# FMC_HPC2.net
KiCad netlist of a schematic drawn in Altium Designer
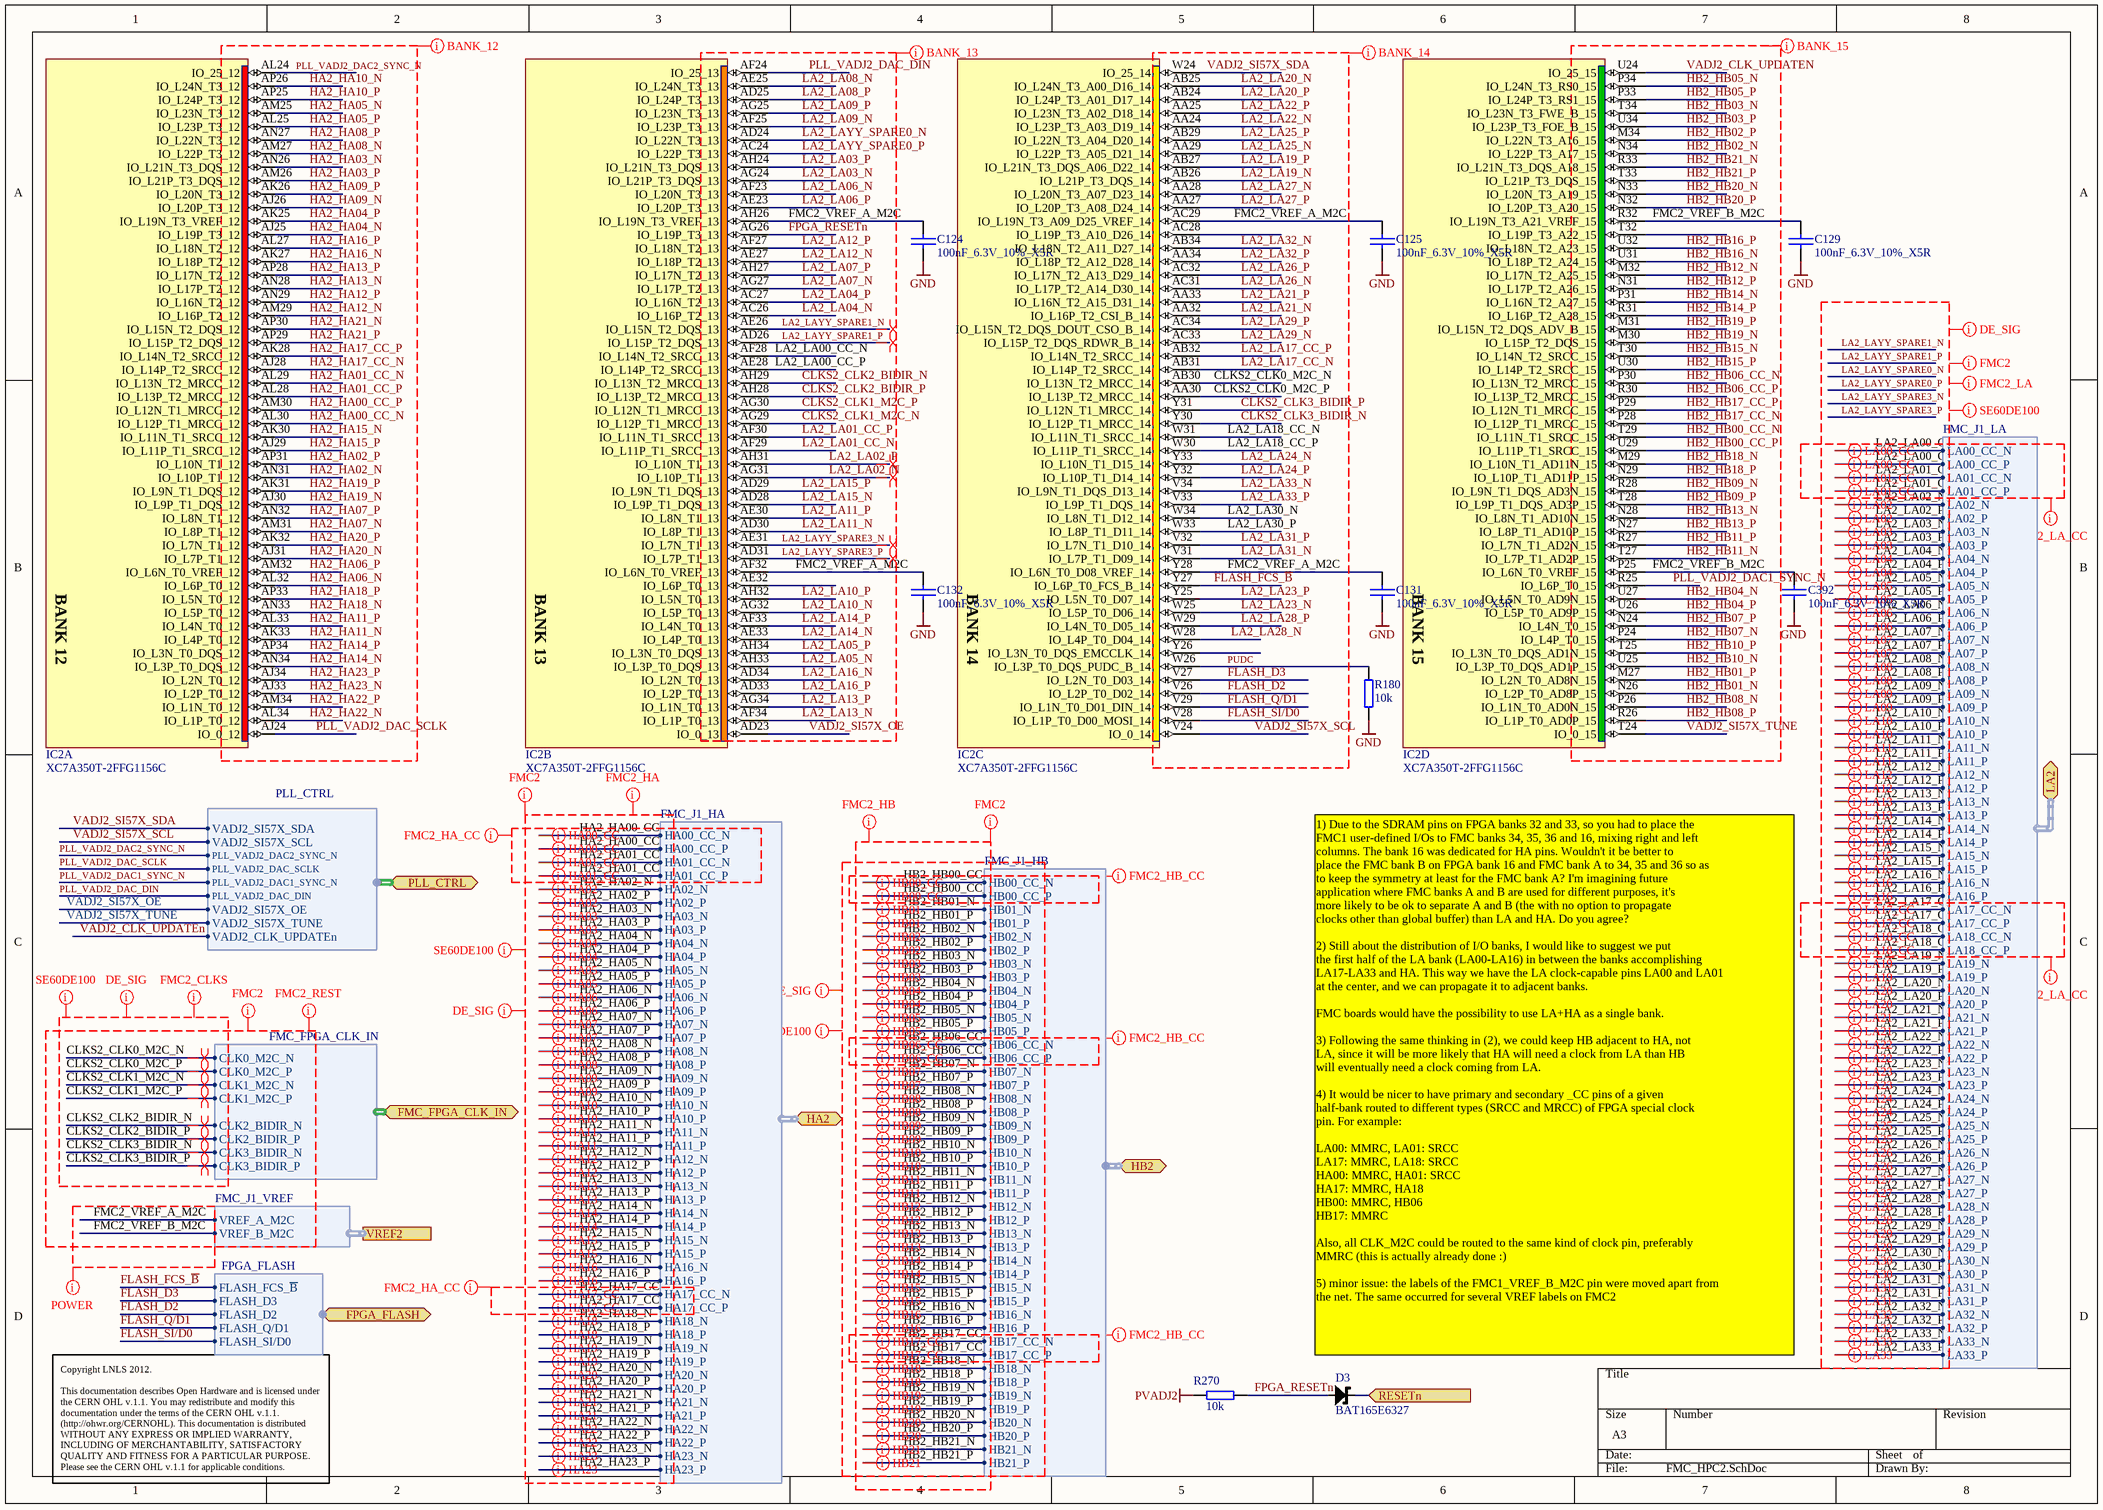
[diagram p0: FMC_HPC2.SchDoc]

(export (version "E")
  (design (tool "Eeschema 10.0.6"))
  (components
    (comp (ref "C124")
      (value "100nF_6.3V_10%_X5R")
      (footprint "0201C")
      (description "Capacitor SMD")
      (libsource (lib "LIBRARY_SCH") (part "CAP_SMD_0201"))
    )
    (comp (ref "C125")
      (value "100nF_6.3V_10%_X5R")
      (footprint "0201C")
      (description "Capacitor SMD")
      (libsource (lib "LIBRARY_SCH") (part "CAP_SMD_0201"))
    )
    (comp (ref "C129")
      (value "100nF_6.3V_10%_X5R")
      (footprint "0201C")
      (description "Capacitor SMD")
      (libsource (lib "LIBRARY_SCH") (part "CAP_SMD_0201"))
    )
    (comp (ref "C131")
      (value "100nF_6.3V_10%_X5R")
      (footprint "0201C")
      (description "Capacitor SMD")
      (libsource (lib "LIBRARY_SCH") (part "CAP_SMD_0201"))
    )
    (comp (ref "C132")
      (value "100nF_6.3V_10%_X5R")
      (footprint "0201C")
      (description "Capacitor SMD")
      (libsource (lib "LIBRARY_SCH") (part "CAP_SMD_0201"))
    )
    (comp (ref "C392")
      (value "100nF_6.3V_10%_X5R")
      (footprint "0201C")
      (description "Capacitor SMD")
      (libsource (lib "LIBRARY_SCH") (part "CAP_SMD_0201"))
    )
    (comp (ref "D3")
      (value "BAT165E6327")
      (footprint "SOD323")
      (description "500mA, 40V, Shottky Diode")
      (libsource (lib "LIBRARY_SCH") (part "D_BAT165"))
    )
    (comp (ref "IC2")
      (value "XC7A350T-2FFG1156C")
      (footprint "BGA1156C100P34X34_3500X3500X335")
      (description "Artix-6 FPGA, 16 GTPs, 600 User I/Os, 1156-Pin BGA, Speed Grade 2, Commercial Grade, Pb-Free")
      (fields (field (name "MANUFACTURER") "XILINX") (field (name "AUTHOR") "CERN DEM JLC"))
      (libsource (lib "AMC_FMC_Carrier") (part "XC7A350T-2FFG1156C"))
    )
    (comp (ref "R180")
      (value "10k")
      (footprint "0402R")
      (description "SMD Resistor")
      (libsource (lib "LIBRARY_SCH") (part "RES_0402"))
    )
    (comp (ref "R270")
      (value "10k")
      (footprint "0402R")
      (description "SMD Resistor")
      (libsource (lib "LIBRARY_SCH") (part "RES_0402"))
    )
  )
  (nets
    (net (code "8") (name "/CLKS2_CLK0_M2C_N") (class "Default")
      (node (ref "IC2") (pin "AB30") (pinfunction "IO_L13N_T2_MRCC_14_AB30") (pintype "bidirectional"))
    )
    (net (code "9") (name "/CLKS2_CLK0_M2C_P") (class "Default")
      (node (ref "IC2") (pin "AA30") (pinfunction "IO_L13P_T2_MRCC_14_AA30") (pintype "bidirectional"))
    )
    (net (code "10") (name "/CLKS2_CLK1_M2C_N") (class "Default")
      (node (ref "IC2") (pin "AG29") (pinfunction "IO_L12P_T1_MRCC_13_AG29") (pintype "bidirectional"))
    )
    (net (code "11") (name "/CLKS2_CLK1_M2C_P") (class "Default")
      (node (ref "IC2") (pin "AG30") (pinfunction "IO_L12N_T1_MRCC_13_AG30") (pintype "bidirectional"))
    )
    (net (code "12") (name "/CLKS2_CLK2_BIDIR_N") (class "Default")
      (node (ref "IC2") (pin "AH29") (pinfunction "IO_L13N_T2_MRCC_13_AH29") (pintype "bidirectional"))
    )
    (net (code "13") (name "/CLKS2_CLK2_BIDIR_P") (class "Default")
      (node (ref "IC2") (pin "AH28") (pinfunction "IO_L13P_T2_MRCC_13_AH28") (pintype "bidirectional"))
    )
    (net (code "14") (name "/CLKS2_CLK3_BIDIR_N") (class "Default")
      (node (ref "IC2") (pin "Y30") (pinfunction "IO_L12P_T1_MRCC_14_Y30") (pintype "bidirectional"))
    )
    (net (code "15") (name "/CLKS2_CLK3_BIDIR_P") (class "Default")
      (node (ref "IC2") (pin "Y31") (pinfunction "IO_L12N_T1_MRCC_14_Y31") (pintype "bidirectional"))
    )
    (net (code "16") (name "/FLASH_D2") (class "Default")
      (node (ref "IC2") (pin "V26") (pinfunction "IO_L2P_T0_D02_14_V26") (pintype "bidirectional"))
    )
    (net (code "17") (name "/FLASH_D3") (class "Default")
      (node (ref "IC2") (pin "V27") (pinfunction "IO_L2N_T0_D03_14_V27") (pintype "bidirectional"))
    )
    (net (code "18") (name "/FLASH_FCS_~{B}") (class "Default")
      (node (ref "IC2") (pin "Y27") (pinfunction "IO_L6P_T0_FCS_B_14_Y27") (pintype "bidirectional"))
    )
    (net (code "19") (name "/FLASH_Q{slash}D1") (class "Default")
      (node (ref "IC2") (pin "V29") (pinfunction "IO_L1N_T0_D01_DIN_14_V29") (pintype "bidirectional"))
    )
    (net (code "20") (name "/FLASH_SI{slash}D0") (class "Default")
      (node (ref "IC2") (pin "V28") (pinfunction "IO_L1P_T0_D00_MOSI_14_V28") (pintype "bidirectional"))
    )
    (net (code "21") (name "/FMC2_VREF_A_M2C") (class "Default")
      (node (ref "C124") (pin "1") (pinfunction "1_1") (pintype "passive"))
      (node (ref "C125") (pin "1") (pinfunction "1_1") (pintype "passive"))
      (node (ref "C131") (pin "1") (pinfunction "1_1") (pintype "passive"))
      (node (ref "C132") (pin "1") (pinfunction "1_1") (pintype "passive"))
      (node (ref "IC2") (pin "AC29") (pinfunction "IO_L19N_T3_A09_D25_VREF_14_AC29") (pintype "bidirectional"))
      (node (ref "IC2") (pin "AF32") (pinfunction "IO_L6N_T0_VREF_13_AF32") (pintype "bidirectional"))
      (node (ref "IC2") (pin "AH26") (pinfunction "IO_L19N_T3_VREF_13_AH26") (pintype "bidirectional"))
      (node (ref "IC2") (pin "Y28") (pinfunction "IO_L6N_T0_D08_VREF_14_Y28") (pintype "bidirectional"))
    )
    (net (code "22") (name "/FMC2_VREF_B_M2C") (class "Default")
      (node (ref "C129") (pin "1") (pinfunction "1_1") (pintype "passive"))
      (node (ref "C392") (pin "1") (pinfunction "1_1") (pintype "passive"))
      (node (ref "IC2") (pin "P25") (pinfunction "IO_L6N_T0_VREF_15_P25") (pintype "bidirectional"))
      (node (ref "IC2") (pin "R32") (pinfunction "IO_L19N_T3_A21_VREF_15_R32") (pintype "bidirectional"))
    )
    (net (code "23") (name "/FPGA_RESETn") (class "Default")
      (node (ref "D3") (pin "A") (pinfunction "A_A") (pintype "passive"))
      (node (ref "IC2") (pin "AG26") (pinfunction "IO_L19P_T3_13_AG26") (pintype "bidirectional"))
      (node (ref "R270") (pin "2") (pinfunction "2_2") (pintype "passive"))
    )
    (net (code "24") (name "/HA2_HA00_CC_N") (class "Default")
      (node (ref "IC2") (pin "AL30") (pinfunction "IO_L12P_T1_MRCC_12_AL30") (pintype "bidirectional"))
    )
    (net (code "25") (name "/HA2_HA00_CC_P") (class "Default")
      (node (ref "IC2") (pin "AM30") (pinfunction "IO_L12N_T1_MRCC_12_AM30") (pintype "bidirectional"))
    )
    (net (code "26") (name "/HA2_HA01_CC_N") (class "Default")
      (node (ref "IC2") (pin "AL29") (pinfunction "IO_L13N_T2_MRCC_12_AL29") (pintype "bidirectional"))
    )
    (net (code "27") (name "/HA2_HA01_CC_P") (class "Default")
      (node (ref "IC2") (pin "AL28") (pinfunction "IO_L13P_T2_MRCC_12_AL28") (pintype "bidirectional"))
    )
    (net (code "28") (name "/HA2_HA02_N") (class "Default")
      (node (ref "IC2") (pin "AN31") (pinfunction "IO_L10P_T1_12_AN31") (pintype "bidirectional"))
    )
    (net (code "29") (name "/HA2_HA02_P") (class "Default")
      (node (ref "IC2") (pin "AP31") (pinfunction "IO_L10N_T1_12_AP31") (pintype "bidirectional"))
    )
    (net (code "30") (name "/HA2_HA03_N") (class "Default")
      (node (ref "IC2") (pin "AN26") (pinfunction "IO_L21N_T3_DQS_12_AN26") (pintype "bidirectional"))
    )
    (net (code "31") (name "/HA2_HA03_P") (class "Default")
      (node (ref "IC2") (pin "AM26") (pinfunction "IO_L21P_T3_DQS_12_AM26") (pintype "bidirectional"))
    )
    (net (code "32") (name "/HA2_HA04_N") (class "Default")
      (node (ref "IC2") (pin "AJ25") (pinfunction "IO_L19P_T3_12_AJ25") (pintype "bidirectional"))
    )
    (net (code "33") (name "/HA2_HA04_P") (class "Default")
      (node (ref "IC2") (pin "AK25") (pinfunction "IO_L19N_T3_VREF_12_AK25") (pintype "bidirectional"))
    )
    (net (code "34") (name "/HA2_HA05_N") (class "Default")
      (node (ref "IC2") (pin "AM25") (pinfunction "IO_L23N_T3_12_AM25") (pintype "bidirectional"))
    )
    (net (code "35") (name "/HA2_HA05_P") (class "Default")
      (node (ref "IC2") (pin "AL25") (pinfunction "IO_L23P_T3_12_AL25") (pintype "bidirectional"))
    )
    (net (code "36") (name "/HA2_HA06_N") (class "Default")
      (node (ref "IC2") (pin "AL32") (pinfunction "IO_L6P_T0_12_AL32") (pintype "bidirectional"))
    )
    (net (code "37") (name "/HA2_HA06_P") (class "Default")
      (node (ref "IC2") (pin "AM32") (pinfunction "IO_L6N_T0_VREF_12_AM32") (pintype "bidirectional"))
    )
    (net (code "38") (name "/HA2_HA07_N") (class "Default")
      (node (ref "IC2") (pin "AM31") (pinfunction "IO_L8P_T1_12_AM31") (pintype "bidirectional"))
    )
    (net (code "39") (name "/HA2_HA07_P") (class "Default")
      (node (ref "IC2") (pin "AN32") (pinfunction "IO_L8N_T1_12_AN32") (pintype "bidirectional"))
    )
    (net (code "40") (name "/HA2_HA08_N") (class "Default")
      (node (ref "IC2") (pin "AM27") (pinfunction "IO_L22P_T3_12_AM27") (pintype "bidirectional"))
    )
    (net (code "41") (name "/HA2_HA08_P") (class "Default")
      (node (ref "IC2") (pin "AN27") (pinfunction "IO_L22N_T3_12_AN27") (pintype "bidirectional"))
    )
    (net (code "42") (name "/HA2_HA09_N") (class "Default")
      (node (ref "IC2") (pin "AJ26") (pinfunction "IO_L20P_T3_12_AJ26") (pintype "bidirectional"))
    )
    (net (code "43") (name "/HA2_HA09_P") (class "Default")
      (node (ref "IC2") (pin "AK26") (pinfunction "IO_L20N_T3_12_AK26") (pintype "bidirectional"))
    )
    (net (code "44") (name "/HA2_HA10_N") (class "Default")
      (node (ref "IC2") (pin "AP26") (pinfunction "IO_L24N_T3_12_AP26") (pintype "bidirectional"))
    )
    (net (code "45") (name "/HA2_HA10_P") (class "Default")
      (node (ref "IC2") (pin "AP25") (pinfunction "IO_L24P_T3_12_AP25") (pintype "bidirectional"))
    )
    (net (code "46") (name "/HA2_HA11_N") (class "Default")
      (node (ref "IC2") (pin "AK33") (pinfunction "IO_L4P_T0_12_AK33") (pintype "bidirectional"))
    )
    (net (code "47") (name "/HA2_HA11_P") (class "Default")
      (node (ref "IC2") (pin "AL33") (pinfunction "IO_L4N_T0_12_AL33") (pintype "bidirectional"))
    )
    (net (code "48") (name "/HA2_HA12_N") (class "Default")
      (node (ref "IC2") (pin "AM29") (pinfunction "IO_L16P_T2_12_AM29") (pintype "bidirectional"))
    )
    (net (code "49") (name "/HA2_HA12_P") (class "Default")
      (node (ref "IC2") (pin "AN29") (pinfunction "IO_L16N_T2_12_AN29") (pintype "bidirectional"))
    )
    (net (code "50") (name "/HA2_HA13_N") (class "Default")
      (node (ref "IC2") (pin "AN28") (pinfunction "IO_L17P_T2_12_AN28") (pintype "bidirectional"))
    )
    (net (code "51") (name "/HA2_HA13_P") (class "Default")
      (node (ref "IC2") (pin "AP28") (pinfunction "IO_L17N_T2_12_AP28") (pintype "bidirectional"))
    )
    (net (code "52") (name "/HA2_HA14_N") (class "Default")
      (node (ref "IC2") (pin "AN34") (pinfunction "IO_L3P_T0_DQS_12_AN34") (pintype "bidirectional"))
    )
    (net (code "53") (name "/HA2_HA14_P") (class "Default")
      (node (ref "IC2") (pin "AP34") (pinfunction "IO_L3N_T0_DQS_12_AP34") (pintype "bidirectional"))
    )
    (net (code "54") (name "/HA2_HA15_N") (class "Default")
      (node (ref "IC2") (pin "AK30") (pinfunction "IO_L11N_T1_SRCC_12_AK30") (pintype "bidirectional"))
    )
    (net (code "55") (name "/HA2_HA15_P") (class "Default")
      (node (ref "IC2") (pin "AJ29") (pinfunction "IO_L11P_T1_SRCC_12_AJ29") (pintype "bidirectional"))
    )
    (net (code "56") (name "/HA2_HA16_N") (class "Default")
      (node (ref "IC2") (pin "AK27") (pinfunction "IO_L18P_T2_12_AK27") (pintype "bidirectional"))
    )
    (net (code "57") (name "/HA2_HA16_P") (class "Default")
      (node (ref "IC2") (pin "AL27") (pinfunction "IO_L18N_T2_12_AL27") (pintype "bidirectional"))
    )
    (net (code "58") (name "/HA2_HA17_CC_N") (class "Default")
      (node (ref "IC2") (pin "AJ28") (pinfunction "IO_L14P_T2_SRCC_12_AJ28") (pintype "bidirectional"))
    )
    (net (code "59") (name "/HA2_HA17_CC_P") (class "Default")
      (node (ref "IC2") (pin "AK28") (pinfunction "IO_L14N_T2_SRCC_12_AK28") (pintype "bidirectional"))
    )
    (net (code "60") (name "/HA2_HA18_N") (class "Default")
      (node (ref "IC2") (pin "AN33") (pinfunction "IO_L5P_T0_12_AN33") (pintype "bidirectional"))
    )
    (net (code "61") (name "/HA2_HA18_P") (class "Default")
      (node (ref "IC2") (pin "AP33") (pinfunction "IO_L5N_T0_12_AP33") (pintype "bidirectional"))
    )
    (net (code "62") (name "/HA2_HA19_N") (class "Default")
      (node (ref "IC2") (pin "AJ30") (pinfunction "IO_L9P_T1_DQS_12_AJ30") (pintype "bidirectional"))
    )
    (net (code "63") (name "/HA2_HA19_P") (class "Default")
      (node (ref "IC2") (pin "AK31") (pinfunction "IO_L9N_T1_DQS_12_AK31") (pintype "bidirectional"))
    )
    (net (code "64") (name "/HA2_HA20_N") (class "Default")
      (node (ref "IC2") (pin "AJ31") (pinfunction "IO_L7P_T1_12_AJ31") (pintype "bidirectional"))
    )
    (net (code "65") (name "/HA2_HA20_P") (class "Default")
      (node (ref "IC2") (pin "AK32") (pinfunction "IO_L7N_T1_12_AK32") (pintype "bidirectional"))
    )
    (net (code "66") (name "/HA2_HA21_N") (class "Default")
      (node (ref "IC2") (pin "AP30") (pinfunction "IO_L15N_T2_DQS_12_AP30") (pintype "bidirectional"))
    )
    (net (code "67") (name "/HA2_HA21_P") (class "Default")
      (node (ref "IC2") (pin "AP29") (pinfunction "IO_L15P_T2_DQS_12_AP29") (pintype "bidirectional"))
    )
    (net (code "68") (name "/HA2_HA22_N") (class "Default")
      (node (ref "IC2") (pin "AL34") (pinfunction "IO_L1P_T0_12_AL34") (pintype "bidirectional"))
    )
    (net (code "69") (name "/HA2_HA22_P") (class "Default")
      (node (ref "IC2") (pin "AM34") (pinfunction "IO_L1N_T0_12_AM34") (pintype "bidirectional"))
    )
    (net (code "70") (name "/HA2_HA23_N") (class "Default")
      (node (ref "IC2") (pin "AJ33") (pinfunction "IO_L2P_T0_12_AJ33") (pintype "bidirectional"))
    )
    (net (code "71") (name "/HA2_HA23_P") (class "Default")
      (node (ref "IC2") (pin "AJ34") (pinfunction "IO_L2N_T0_12_AJ34") (pintype "bidirectional"))
    )
    (net (code "72") (name "/HB2_HB00_CC_N") (class "Default")
      (node (ref "IC2") (pin "T29") (pinfunction "IO_L11N_T1_SRCC_15_T29") (pintype "bidirectional"))
    )
    (net (code "73") (name "/HB2_HB00_CC_P") (class "Default")
      (node (ref "IC2") (pin "U29") (pinfunction "IO_L11P_T1_SRCC_15_U29") (pintype "bidirectional"))
    )
    (net (code "74") (name "/HB2_HB01_N") (class "Default")
      (node (ref "IC2") (pin "N26") (pinfunction "IO_L2P_T0_AD8P_15_N26") (pintype "bidirectional"))
    )
    (net (code "75") (name "/HB2_HB01_P") (class "Default")
      (node (ref "IC2") (pin "M27") (pinfunction "IO_L2N_T0_AD8N_15_M27") (pintype "bidirectional"))
    )
    (net (code "76") (name "/HB2_HB02_N") (class "Default")
      (node (ref "IC2") (pin "N34") (pinfunction "IO_L22P_T3_A17_15_N34") (pintype "bidirectional"))
    )
    (net (code "77") (name "/HB2_HB02_P") (class "Default")
      (node (ref "IC2") (pin "M34") (pinfunction "IO_L22N_T3_A16_15_M34") (pintype "bidirectional"))
    )
    (net (code "78") (name "/HB2_HB03_N") (class "Default")
      (node (ref "IC2") (pin "T34") (pinfunction "IO_L23N_T3_FWE_B_15_T34") (pintype "bidirectional"))
    )
    (net (code "79") (name "/HB2_HB03_P") (class "Default")
      (node (ref "IC2") (pin "U34") (pinfunction "IO_L23P_T3_FOE_B_15_U34") (pintype "bidirectional"))
    )
    (net (code "80") (name "/HB2_HB04_N") (class "Default")
      (node (ref "IC2") (pin "U27") (pinfunction "IO_L5N_T0_AD9N_15_U27") (pintype "bidirectional"))
    )
    (net (code "81") (name "/HB2_HB04_P") (class "Default")
      (node (ref "IC2") (pin "U26") (pinfunction "IO_L5P_T0_AD9P_15_U26") (pintype "bidirectional"))
    )
    (net (code "82") (name "/HB2_HB05_N") (class "Default")
      (node (ref "IC2") (pin "P34") (pinfunction "IO_L24N_T3_RS0_15_P34") (pintype "bidirectional"))
    )
    (net (code "83") (name "/HB2_HB05_P") (class "Default")
      (node (ref "IC2") (pin "P33") (pinfunction "IO_L24P_T3_RS1_15_P33") (pintype "bidirectional"))
    )
    (net (code "84") (name "/HB2_HB06_CC_N") (class "Default")
      (node (ref "IC2") (pin "P30") (pinfunction "IO_L13N_T2_MRCC_15_P30") (pintype "bidirectional"))
    )
    (net (code "85") (name "/HB2_HB06_CC_P") (class "Default")
      (node (ref "IC2") (pin "R30") (pinfunction "IO_L13P_T2_MRCC_15_R30") (pintype "bidirectional"))
    )
    (net (code "86") (name "/HB2_HB07_N") (class "Default")
      (node (ref "IC2") (pin "P24") (pinfunction "IO_L4P_T0_15_P24") (pintype "bidirectional"))
    )
    (net (code "87") (name "/HB2_HB07_P") (class "Default")
      (node (ref "IC2") (pin "N24") (pinfunction "IO_L4N_T0_15_N24") (pintype "bidirectional"))
    )
    (net (code "88") (name "/HB2_HB08_N") (class "Default")
      (node (ref "IC2") (pin "P26") (pinfunction "IO_L1N_T0_AD0N_15_P26") (pintype "bidirectional"))
    )
    (net (code "89") (name "/HB2_HB08_P") (class "Default")
      (node (ref "IC2") (pin "R26") (pinfunction "IO_L1P_T0_AD0P_15_R26") (pintype "bidirectional"))
    )
    (net (code "90") (name "/HB2_HB09_N") (class "Default")
      (node (ref "IC2") (pin "R28") (pinfunction "IO_L9N_T1_DQS_AD3N_15_R28") (pintype "bidirectional"))
    )
    (net (code "91") (name "/HB2_HB09_P") (class "Default")
      (node (ref "IC2") (pin "T28") (pinfunction "IO_L9P_T1_DQS_AD3P_15_T28") (pintype "bidirectional"))
    )
    (net (code "92") (name "/HB2_HB10_N") (class "Default")
      (node (ref "IC2") (pin "U25") (pinfunction "IO_L3P_T0_DQS_AD1P_15_U25") (pintype "bidirectional"))
    )
    (net (code "93") (name "/HB2_HB10_P") (class "Default")
      (node (ref "IC2") (pin "T25") (pinfunction "IO_L3N_T0_DQS_AD1N_15_T25") (pintype "bidirectional"))
    )
    (net (code "94") (name "/HB2_HB11_N") (class "Default")
      (node (ref "IC2") (pin "T27") (pinfunction "IO_L7P_T1_AD2P_15_T27") (pintype "bidirectional"))
    )
    (net (code "95") (name "/HB2_HB11_P") (class "Default")
      (node (ref "IC2") (pin "R27") (pinfunction "IO_L7N_T1_AD2N_15_R27") (pintype "bidirectional"))
    )
    (net (code "96") (name "/HB2_HB12_N") (class "Default")
      (node (ref "IC2") (pin "M32") (pinfunction "IO_L17N_T2_A25_15_M32") (pintype "bidirectional"))
    )
    (net (code "97") (name "/HB2_HB12_P") (class "Default")
      (node (ref "IC2") (pin "N31") (pinfunction "IO_L17P_T2_A26_15_N31") (pintype "bidirectional"))
    )
    (net (code "98") (name "/HB2_HB13_N") (class "Default")
      (node (ref "IC2") (pin "N28") (pinfunction "IO_L8N_T1_AD10N_15_N28") (pintype "bidirectional"))
    )
    (net (code "99") (name "/HB2_HB13_P") (class "Default")
      (node (ref "IC2") (pin "N27") (pinfunction "IO_L8P_T1_AD10P_15_N27") (pintype "bidirectional"))
    )
    (net (code "100") (name "/HB2_HB14_N") (class "Default")
      (node (ref "IC2") (pin "P31") (pinfunction "IO_L16N_T2_A27_15_P31") (pintype "bidirectional"))
    )
    (net (code "101") (name "/HB2_HB14_P") (class "Default")
      (node (ref "IC2") (pin "R31") (pinfunction "IO_L16P_T2_A28_15_R31") (pintype "bidirectional"))
    )
    (net (code "102") (name "/HB2_HB15_N") (class "Default")
      (node (ref "IC2") (pin "T30") (pinfunction "IO_L14N_T2_SRCC_15_T30") (pintype "bidirectional"))
    )
    (net (code "103") (name "/HB2_HB15_P") (class "Default")
      (node (ref "IC2") (pin "U30") (pinfunction "IO_L14P_T2_SRCC_15_U30") (pintype "bidirectional"))
    )
    (net (code "104") (name "/HB2_HB16_N") (class "Default")
      (node (ref "IC2") (pin "U31") (pinfunction "IO_L18P_T2_A24_15_U31") (pintype "bidirectional"))
    )
    (net (code "105") (name "/HB2_HB16_P") (class "Default")
      (node (ref "IC2") (pin "U32") (pinfunction "IO_L18N_T2_A23_15_U32") (pintype "bidirectional"))
    )
    (net (code "106") (name "/HB2_HB17_CC_N") (class "Default")
      (node (ref "IC2") (pin "P28") (pinfunction "IO_L12P_T1_MRCC_15_P28") (pintype "bidirectional"))
    )
    (net (code "107") (name "/HB2_HB17_CC_P") (class "Default")
      (node (ref "IC2") (pin "P29") (pinfunction "IO_L12N_T1_MRCC_15_P29") (pintype "bidirectional"))
    )
    (net (code "108") (name "/HB2_HB18_N") (class "Default")
      (node (ref "IC2") (pin "M29") (pinfunction "IO_L10N_T1_AD11N_15_M29") (pintype "bidirectional"))
    )
    (net (code "109") (name "/HB2_HB18_P") (class "Default")
      (node (ref "IC2") (pin "N29") (pinfunction "IO_L10P_T1_AD11P_15_N29") (pintype "bidirectional"))
    )
    (net (code "110") (name "/HB2_HB19_N") (class "Default")
      (node (ref "IC2") (pin "M30") (pinfunction "IO_L15P_T2_DQS_15_M30") (pintype "bidirectional"))
    )
    (net (code "111") (name "/HB2_HB19_P") (class "Default")
      (node (ref "IC2") (pin "M31") (pinfunction "IO_L15N_T2_DQS_ADV_B_15_M31") (pintype "bidirectional"))
    )
    (net (code "112") (name "/HB2_HB20_N") (class "Default")
      (node (ref "IC2") (pin "N33") (pinfunction "IO_L20N_T3_A19_15_N33") (pintype "bidirectional"))
    )
    (net (code "113") (name "/HB2_HB20_P") (class "Default")
      (node (ref "IC2") (pin "N32") (pinfunction "IO_L20P_T3_A20_15_N32") (pintype "bidirectional"))
    )
    (net (code "114") (name "/HB2_HB21_N") (class "Default")
      (node (ref "IC2") (pin "R33") (pinfunction "IO_L21N_T3_DQS_A18_15_R33") (pintype "bidirectional"))
    )
    (net (code "115") (name "/HB2_HB21_P") (class "Default")
      (node (ref "IC2") (pin "T33") (pinfunction "IO_L21P_T3_DQS_15_T33") (pintype "bidirectional"))
    )
    (net (code "116") (name "/LA2_LA00_CC_N") (class "Default")
      (node (ref "IC2") (pin "AF28") (pinfunction "IO_L14N_T2_SRCC_13_AF28") (pintype "bidirectional"))
    )
    (net (code "117") (name "/LA2_LA00_CC_P") (class "Default")
      (node (ref "IC2") (pin "AE28") (pinfunction "IO_L14P_T2_SRCC_13_AE28") (pintype "bidirectional"))
    )
    (net (code "118") (name "/LA2_LA01_CC_N") (class "Default")
      (node (ref "IC2") (pin "AF29") (pinfunction "IO_L11P_T1_SRCC_13_AF29") (pintype "bidirectional"))
    )
    (net (code "119") (name "/LA2_LA01_CC_P") (class "Default")
      (node (ref "IC2") (pin "AF30") (pinfunction "IO_L11N_T1_SRCC_13_AF30") (pintype "bidirectional"))
    )
    (net (code "120") (name "/LA2_LA02_N") (class "Default")
      (node (ref "IC2") (pin "AG31") (pinfunction "IO_L10P_T1_13_AG31") (pintype "bidirectional"))
    )
    (net (code "121") (name "/LA2_LA02_P") (class "Default")
      (node (ref "IC2") (pin "AH31") (pinfunction "IO_L10N_T1_13_AH31") (pintype "bidirectional"))
    )
    (net (code "122") (name "/LA2_LA03_N") (class "Default")
      (node (ref "IC2") (pin "AG24") (pinfunction "IO_L21P_T3_DQS_13_AG24") (pintype "bidirectional"))
    )
    (net (code "123") (name "/LA2_LA03_P") (class "Default")
      (node (ref "IC2") (pin "AH24") (pinfunction "IO_L21N_T3_DQS_13_AH24") (pintype "bidirectional"))
    )
    (net (code "124") (name "/LA2_LA04_N") (class "Default")
      (node (ref "IC2") (pin "AC26") (pinfunction "IO_L16P_T2_13_AC26") (pintype "bidirectional"))
    )
    (net (code "125") (name "/LA2_LA04_P") (class "Default")
      (node (ref "IC2") (pin "AC27") (pinfunction "IO_L16N_T2_13_AC27") (pintype "bidirectional"))
    )
    (net (code "126") (name "/LA2_LA05_N") (class "Default")
      (node (ref "IC2") (pin "AH33") (pinfunction "IO_L3P_T0_DQS_13_AH33") (pintype "bidirectional"))
    )
    (net (code "127") (name "/LA2_LA05_P") (class "Default")
      (node (ref "IC2") (pin "AH34") (pinfunction "IO_L3N_T0_DQS_13_AH34") (pintype "bidirectional"))
    )
    (net (code "128") (name "/LA2_LA06_N") (class "Default")
      (node (ref "IC2") (pin "AF23") (pinfunction "IO_L20N_T3_13_AF23") (pintype "bidirectional"))
    )
    (net (code "129") (name "/LA2_LA06_P") (class "Default")
      (node (ref "IC2") (pin "AE23") (pinfunction "IO_L20P_T3_13_AE23") (pintype "bidirectional"))
    )
    (net (code "130") (name "/LA2_LA07_N") (class "Default")
      (node (ref "IC2") (pin "AG27") (pinfunction "IO_L17P_T2_13_AG27") (pintype "bidirectional"))
    )
    (net (code "131") (name "/LA2_LA07_P") (class "Default")
      (node (ref "IC2") (pin "AH27") (pinfunction "IO_L17N_T2_13_AH27") (pintype "bidirectional"))
    )
    (net (code "132") (name "/LA2_LA08_N") (class "Default")
      (node (ref "IC2") (pin "AE25") (pinfunction "IO_L24N_T3_13_AE25") (pintype "bidirectional"))
    )
    (net (code "133") (name "/LA2_LA08_P") (class "Default")
      (node (ref "IC2") (pin "AD25") (pinfunction "IO_L24P_T3_13_AD25") (pintype "bidirectional"))
    )
    (net (code "134") (name "/LA2_LA09_N") (class "Default")
      (node (ref "IC2") (pin "AF25") (pinfunction "IO_L23P_T3_13_AF25") (pintype "bidirectional"))
    )
    (net (code "135") (name "/LA2_LA09_P") (class "Default")
      (node (ref "IC2") (pin "AG25") (pinfunction "IO_L23N_T3_13_AG25") (pintype "bidirectional"))
    )
    (net (code "136") (name "/LA2_LA10_N") (class "Default")
      (node (ref "IC2") (pin "AG32") (pinfunction "IO_L5P_T0_13_AG32") (pintype "bidirectional"))
    )
    (net (code "137") (name "/LA2_LA10_P") (class "Default")
      (node (ref "IC2") (pin "AH32") (pinfunction "IO_L5N_T0_13_AH32") (pintype "bidirectional"))
    )
    (net (code "138") (name "/LA2_LA11_N") (class "Default")
      (node (ref "IC2") (pin "AD30") (pinfunction "IO_L8P_T1_13_AD30") (pintype "bidirectional"))
    )
    (net (code "139") (name "/LA2_LA11_P") (class "Default")
      (node (ref "IC2") (pin "AE30") (pinfunction "IO_L8N_T1_13_AE30") (pintype "bidirectional"))
    )
    (net (code "140") (name "/LA2_LA12_N") (class "Default")
      (node (ref "IC2") (pin "AE27") (pinfunction "IO_L18P_T2_13_AE27") (pintype "bidirectional"))
    )
    (net (code "141") (name "/LA2_LA12_P") (class "Default")
      (node (ref "IC2") (pin "AF27") (pinfunction "IO_L18N_T2_13_AF27") (pintype "bidirectional"))
    )
    (net (code "142") (name "/LA2_LA13_N") (class "Default")
      (node (ref "IC2") (pin "AF34") (pinfunction "IO_L1P_T0_13_AF34") (pintype "bidirectional"))
    )
    (net (code "143") (name "/LA2_LA13_P") (class "Default")
      (node (ref "IC2") (pin "AG34") (pinfunction "IO_L1N_T0_13_AG34") (pintype "bidirectional"))
    )
    (net (code "144") (name "/LA2_LA14_N") (class "Default")
      (node (ref "IC2") (pin "AE33") (pinfunction "IO_L4P_T0_13_AE33") (pintype "bidirectional"))
    )
    (net (code "145") (name "/LA2_LA14_P") (class "Default")
      (node (ref "IC2") (pin "AF33") (pinfunction "IO_L4N_T0_13_AF33") (pintype "bidirectional"))
    )
    (net (code "146") (name "/LA2_LA15_N") (class "Default")
      (node (ref "IC2") (pin "AD28") (pinfunction "IO_L9P_T1_DQS_13_AD28") (pintype "bidirectional"))
    )
    (net (code "147") (name "/LA2_LA15_P") (class "Default")
      (node (ref "IC2") (pin "AD29") (pinfunction "IO_L9N_T1_DQS_13_AD29") (pintype "bidirectional"))
    )
    (net (code "148") (name "/LA2_LA16_N") (class "Default")
      (node (ref "IC2") (pin "AD34") (pinfunction "IO_L2N_T0_13_AD34") (pintype "bidirectional"))
    )
    (net (code "149") (name "/LA2_LA16_P") (class "Default")
      (node (ref "IC2") (pin "AD33") (pinfunction "IO_L2P_T0_13_AD33") (pintype "bidirectional"))
    )
    (net (code "150") (name "/LA2_LA17_CC_N") (class "Default")
      (node (ref "IC2") (pin "AB31") (pinfunction "IO_L14P_T2_SRCC_14_AB31") (pintype "bidirectional"))
    )
    (net (code "151") (name "/LA2_LA17_CC_P") (class "Default")
      (node (ref "IC2") (pin "AB32") (pinfunction "IO_L14N_T2_SRCC_14_AB32") (pintype "bidirectional"))
    )
    (net (code "152") (name "/LA2_LA18_CC_N") (class "Default")
      (node (ref "IC2") (pin "W31") (pinfunction "IO_L11N_T1_SRCC_14_W31") (pintype "bidirectional"))
    )
    (net (code "153") (name "/LA2_LA18_CC_P") (class "Default")
      (node (ref "IC2") (pin "W30") (pinfunction "IO_L11P_T1_SRCC_14_W30") (pintype "bidirectional"))
    )
    (net (code "154") (name "/LA2_LA19_N") (class "Default")
      (node (ref "IC2") (pin "AB26") (pinfunction "IO_L21P_T3_DQS_14_AB26") (pintype "bidirectional"))
    )
    (net (code "155") (name "/LA2_LA19_P") (class "Default")
      (node (ref "IC2") (pin "AB27") (pinfunction "IO_L21N_T3_DQS_A06_D22_14_AB27") (pintype "bidirectional"))
    )
    (net (code "156") (name "/LA2_LA20_N") (class "Default")
      (node (ref "IC2") (pin "AB25") (pinfunction "IO_L24N_T3_A00_D16_14_AB25") (pintype "bidirectional"))
    )
    (net (code "157") (name "/LA2_LA20_P") (class "Default")
      (node (ref "IC2") (pin "AB24") (pinfunction "IO_L24P_T3_A01_D17_14_AB24") (pintype "bidirectional"))
    )
    (net (code "158") (name "/LA2_LA21_N") (class "Default")
      (node (ref "IC2") (pin "AA32") (pinfunction "IO_L16P_T2_CSI_B_14_AA32") (pintype "bidirectional"))
    )
    (net (code "159") (name "/LA2_LA21_P") (class "Default")
      (node (ref "IC2") (pin "AA33") (pinfunction "IO_L16N_T2_A15_D31_14_AA33") (pintype "bidirectional"))
    )
    (net (code "160") (name "/LA2_LA22_N") (class "Default")
      (node (ref "IC2") (pin "AA24") (pinfunction "IO_L23P_T3_A03_D19_14_AA24") (pintype "bidirectional"))
    )
    (net (code "161") (name "/LA2_LA22_P") (class "Default")
      (node (ref "IC2") (pin "AA25") (pinfunction "IO_L23N_T3_A02_D18_14_AA25") (pintype "bidirectional"))
    )
    (net (code "162") (name "/LA2_LA23_N") (class "Default")
      (node (ref "IC2") (pin "W25") (pinfunction "IO_L5P_T0_D06_14_W25") (pintype "bidirectional"))
    )
    (net (code "163") (name "/LA2_LA23_P") (class "Default")
      (node (ref "IC2") (pin "Y25") (pinfunction "IO_L5N_T0_D07_14_Y25") (pintype "bidirectional"))
    )
    (net (code "164") (name "/LA2_LA24_N") (class "Default")
      (node (ref "IC2") (pin "Y33") (pinfunction "IO_L10N_T1_D15_14_Y33") (pintype "bidirectional"))
    )
    (net (code "165") (name "/LA2_LA24_P") (class "Default")
      (node (ref "IC2") (pin "Y32") (pinfunction "IO_L10P_T1_D14_14_Y32") (pintype "bidirectional"))
    )
    (net (code "166") (name "/LA2_LA25_N") (class "Default")
      (node (ref "IC2") (pin "AA29") (pinfunction "IO_L22P_T3_A05_D21_14_AA29") (pintype "bidirectional"))
    )
    (net (code "167") (name "/LA2_LA25_P") (class "Default")
      (node (ref "IC2") (pin "AB29") (pinfunction "IO_L22N_T3_A04_D20_14_AB29") (pintype "bidirectional"))
    )
    (net (code "168") (name "/LA2_LA26_N") (class "Default")
      (node (ref "IC2") (pin "AC31") (pinfunction "IO_L17P_T2_A14_D30_14_AC31") (pintype "bidirectional"))
    )
    (net (code "169") (name "/LA2_LA26_P") (class "Default")
      (node (ref "IC2") (pin "AC32") (pinfunction "IO_L17N_T2_A13_D29_14_AC32") (pintype "bidirectional"))
    )
    (net (code "170") (name "/LA2_LA27_N") (class "Default")
      (node (ref "IC2") (pin "AA28") (pinfunction "IO_L20N_T3_A07_D23_14_AA28") (pintype "bidirectional"))
    )
    (net (code "171") (name "/LA2_LA27_P") (class "Default")
      (node (ref "IC2") (pin "AA27") (pinfunction "IO_L20P_T3_A08_D24_14_AA27") (pintype "bidirectional"))
    )
    (net (code "172") (name "/LA2_LA28_N") (class "Default")
      (node (ref "IC2") (pin "W28") (pinfunction "IO_L4P_T0_D04_14_W28") (pintype "bidirectional"))
    )
    (net (code "173") (name "/LA2_LA28_P") (class "Default")
      (node (ref "IC2") (pin "W29") (pinfunction "IO_L4N_T0_D05_14_W29") (pintype "bidirectional"))
    )
    (net (code "174") (name "/LA2_LA29_N") (class "Default")
      (node (ref "IC2") (pin "AC33") (pinfunction "IO_L15P_T2_DQS_RDWR_B_14_AC33") (pintype "bidirectional"))
    )
    (net (code "175") (name "/LA2_LA29_P") (class "Default")
      (node (ref "IC2") (pin "AC34") (pinfunction "IO_L15N_T2_DQS_DOUT_CSO_B_14_AC34") (pintype "bidirectional"))
    )
    (net (code "176") (name "/LA2_LA30_N") (class "Default")
      (node (ref "IC2") (pin "W34") (pinfunction "IO_L8N_T1_D12_14_W34") (pintype "bidirectional"))
    )
    (net (code "177") (name "/LA2_LA30_P") (class "Default")
      (node (ref "IC2") (pin "W33") (pinfunction "IO_L8P_T1_D11_14_W33") (pintype "bidirectional"))
    )
    (net (code "178") (name "/LA2_LA31_N") (class "Default")
      (node (ref "IC2") (pin "V31") (pinfunction "IO_L7P_T1_D09_14_V31") (pintype "bidirectional"))
    )
    (net (code "179") (name "/LA2_LA31_P") (class "Default")
      (node (ref "IC2") (pin "V32") (pinfunction "IO_L7N_T1_D10_14_V32") (pintype "bidirectional"))
    )
    (net (code "180") (name "/LA2_LA32_N") (class "Default")
      (node (ref "IC2") (pin "AB34") (pinfunction "IO_L18N_T2_A11_D27_14_AB34") (pintype "bidirectional"))
    )
    (net (code "181") (name "/LA2_LA32_P") (class "Default")
      (node (ref "IC2") (pin "AA34") (pinfunction "IO_L18P_T2_A12_D28_14_AA34") (pintype "bidirectional"))
    )
    (net (code "182") (name "/LA2_LA33_N") (class "Default")
      (node (ref "IC2") (pin "V34") (pinfunction "IO_L9N_T1_DQS_D13_14_V34") (pintype "bidirectional"))
    )
    (net (code "183") (name "/LA2_LA33_P") (class "Default")
      (node (ref "IC2") (pin "V33") (pinfunction "IO_L9P_T1_DQS_14_V33") (pintype "bidirectional"))
    )
    (net (code "184") (name "/LA2_LAYY_SPARE0_N") (class "Default")
      (node (ref "IC2") (pin "AD24") (pinfunction "IO_L22N_T3_13_AD24") (pintype "bidirectional"))
    )
    (net (code "185") (name "/LA2_LAYY_SPARE0_P") (class "Default")
      (node (ref "IC2") (pin "AC24") (pinfunction "IO_L22P_T3_13_AC24") (pintype "bidirectional"))
    )
    (net (code "186") (name "/LA2_LAYY_SPARE1_N") (class "Default")
      (node (ref "IC2") (pin "AE26") (pinfunction "IO_L15N_T2_DQS_13_AE26") (pintype "bidirectional"))
    )
    (net (code "187") (name "/LA2_LAYY_SPARE1_P") (class "Default")
      (node (ref "IC2") (pin "AD26") (pinfunction "IO_L15P_T2_DQS_13_AD26") (pintype "bidirectional"))
    )
    (net (code "188") (name "/LA2_LAYY_SPARE3_N") (class "Default")
      (node (ref "IC2") (pin "AE31") (pinfunction "IO_L7N_T1_13_AE31") (pintype "bidirectional"))
    )
    (net (code "189") (name "/LA2_LAYY_SPARE3_P") (class "Default")
      (node (ref "IC2") (pin "AD31") (pinfunction "IO_L7P_T1_13_AD31") (pintype "bidirectional"))
    )
    (net (code "190") (name "/PLL_VADJ2_DAC1_SYNC_N") (class "Default")
      (node (ref "IC2") (pin "R25") (pinfunction "IO_L6P_T0_15_R25") (pintype "bidirectional"))
    )
    (net (code "191") (name "/PLL_VADJ2_DAC2_SYNC_N") (class "Default")
      (node (ref "IC2") (pin "AL24") (pinfunction "IO_25_12_AL24") (pintype "bidirectional"))
    )
    (net (code "192") (name "/PLL_VADJ2_DAC_DIN") (class "Default")
      (node (ref "IC2") (pin "AF24") (pinfunction "IO_25_13_AF24") (pintype "bidirectional"))
    )
    (net (code "193") (name "/PLL_VADJ2_DAC_SCLK") (class "Default")
      (node (ref "IC2") (pin "AJ24") (pinfunction "IO_0_12_AJ24") (pintype "bidirectional"))
    )
    (net (code "194") (name "/PUDC") (class "Default")
      (node (ref "IC2") (pin "W26") (pinfunction "IO_L3P_T0_DQS_PUDC_B_14_W26") (pintype "bidirectional"))
      (node (ref "R180") (pin "1") (pinfunction "1_1") (pintype "passive"))
    )
    (net (code "195") (name "/RESETn") (class "Default")
      (node (ref "D3") (pin "K") (pinfunction "K_K") (pintype "passive"))
    )
    (net (code "196") (name "/VADJ2_CLK_UPDATEN") (class "Default")
      (node (ref "IC2") (pin "U24") (pinfunction "IO_25_15_U24") (pintype "bidirectional"))
    )
    (net (code "198") (name "/VADJ2_SI57X_OE") (class "Default")
      (node (ref "IC2") (pin "AD23") (pinfunction "IO_0_13_AD23") (pintype "bidirectional"))
    )
    (net (code "199") (name "/VADJ2_SI57X_SCL") (class "Default")
      (node (ref "IC2") (pin "V24") (pinfunction "IO_0_14_V24") (pintype "bidirectional"))
    )
    (net (code "200") (name "/VADJ2_SI57X_SDA") (class "Default")
      (node (ref "IC2") (pin "W24") (pinfunction "IO_25_14_W24") (pintype "bidirectional"))
    )
    (net (code "201") (name "/VADJ2_SI57X_TUNE") (class "Default")
      (node (ref "IC2") (pin "T24") (pinfunction "IO_0_15_T24") (pintype "bidirectional"))
    )
    (net (code "209") (name "GND") (class "Default")
      (node (ref "C124") (pin "2") (pinfunction "2_2") (pintype "passive"))
      (node (ref "C125") (pin "2") (pinfunction "2_2") (pintype "passive"))
      (node (ref "C129") (pin "2") (pinfunction "2_2") (pintype "passive"))
      (node (ref "C131") (pin "2") (pinfunction "2_2") (pintype "passive"))
      (node (ref "C132") (pin "2") (pinfunction "2_2") (pintype "passive"))
      (node (ref "C392") (pin "2") (pinfunction "2_2") (pintype "passive"))
      (node (ref "R180") (pin "2") (pinfunction "2_2") (pintype "passive"))
    )
    (net (code "210") (name "PVADJ2") (class "Default")
      (node (ref "R270") (pin "1") (pinfunction "1_1") (pintype "passive"))
    )
    (net (code "211") (name "unconnected-(IC2B-IO_L6P_T0_13-PadAE32)") (class "Default")
      (node (ref "IC2") (pin "AE32") (pinfunction "IO_L6P_T0_13_AE32") (pintype "bidirectional"))
    )
    (net (code "212") (name "unconnected-(IC2C-IO_L3N_T0_DQS_EMCCLK_14-PadY26)") (class "Default")
      (node (ref "IC2") (pin "Y26") (pinfunction "IO_L3N_T0_DQS_EMCCLK_14_Y26") (pintype "bidirectional"))
    )
    (net (code "213") (name "unconnected-(IC2C-IO_L19P_T3_A10_D26_14-PadAC28)") (class "Default")
      (node (ref "IC2") (pin "AC28") (pinfunction "IO_L19P_T3_A10_D26_14_AC28") (pintype "bidirectional"))
    )
    (net (code "214") (name "unconnected-(IC2D-IO_L19P_T3_A22_15-PadT32)") (class "Default")
      (node (ref "IC2") (pin "T32") (pinfunction "IO_L19P_T3_A22_15_T32") (pintype "bidirectional"))
    )
  )
)
